# MT-DS_v1.net
KiCad netlist of a schematic drawn in EAGLE
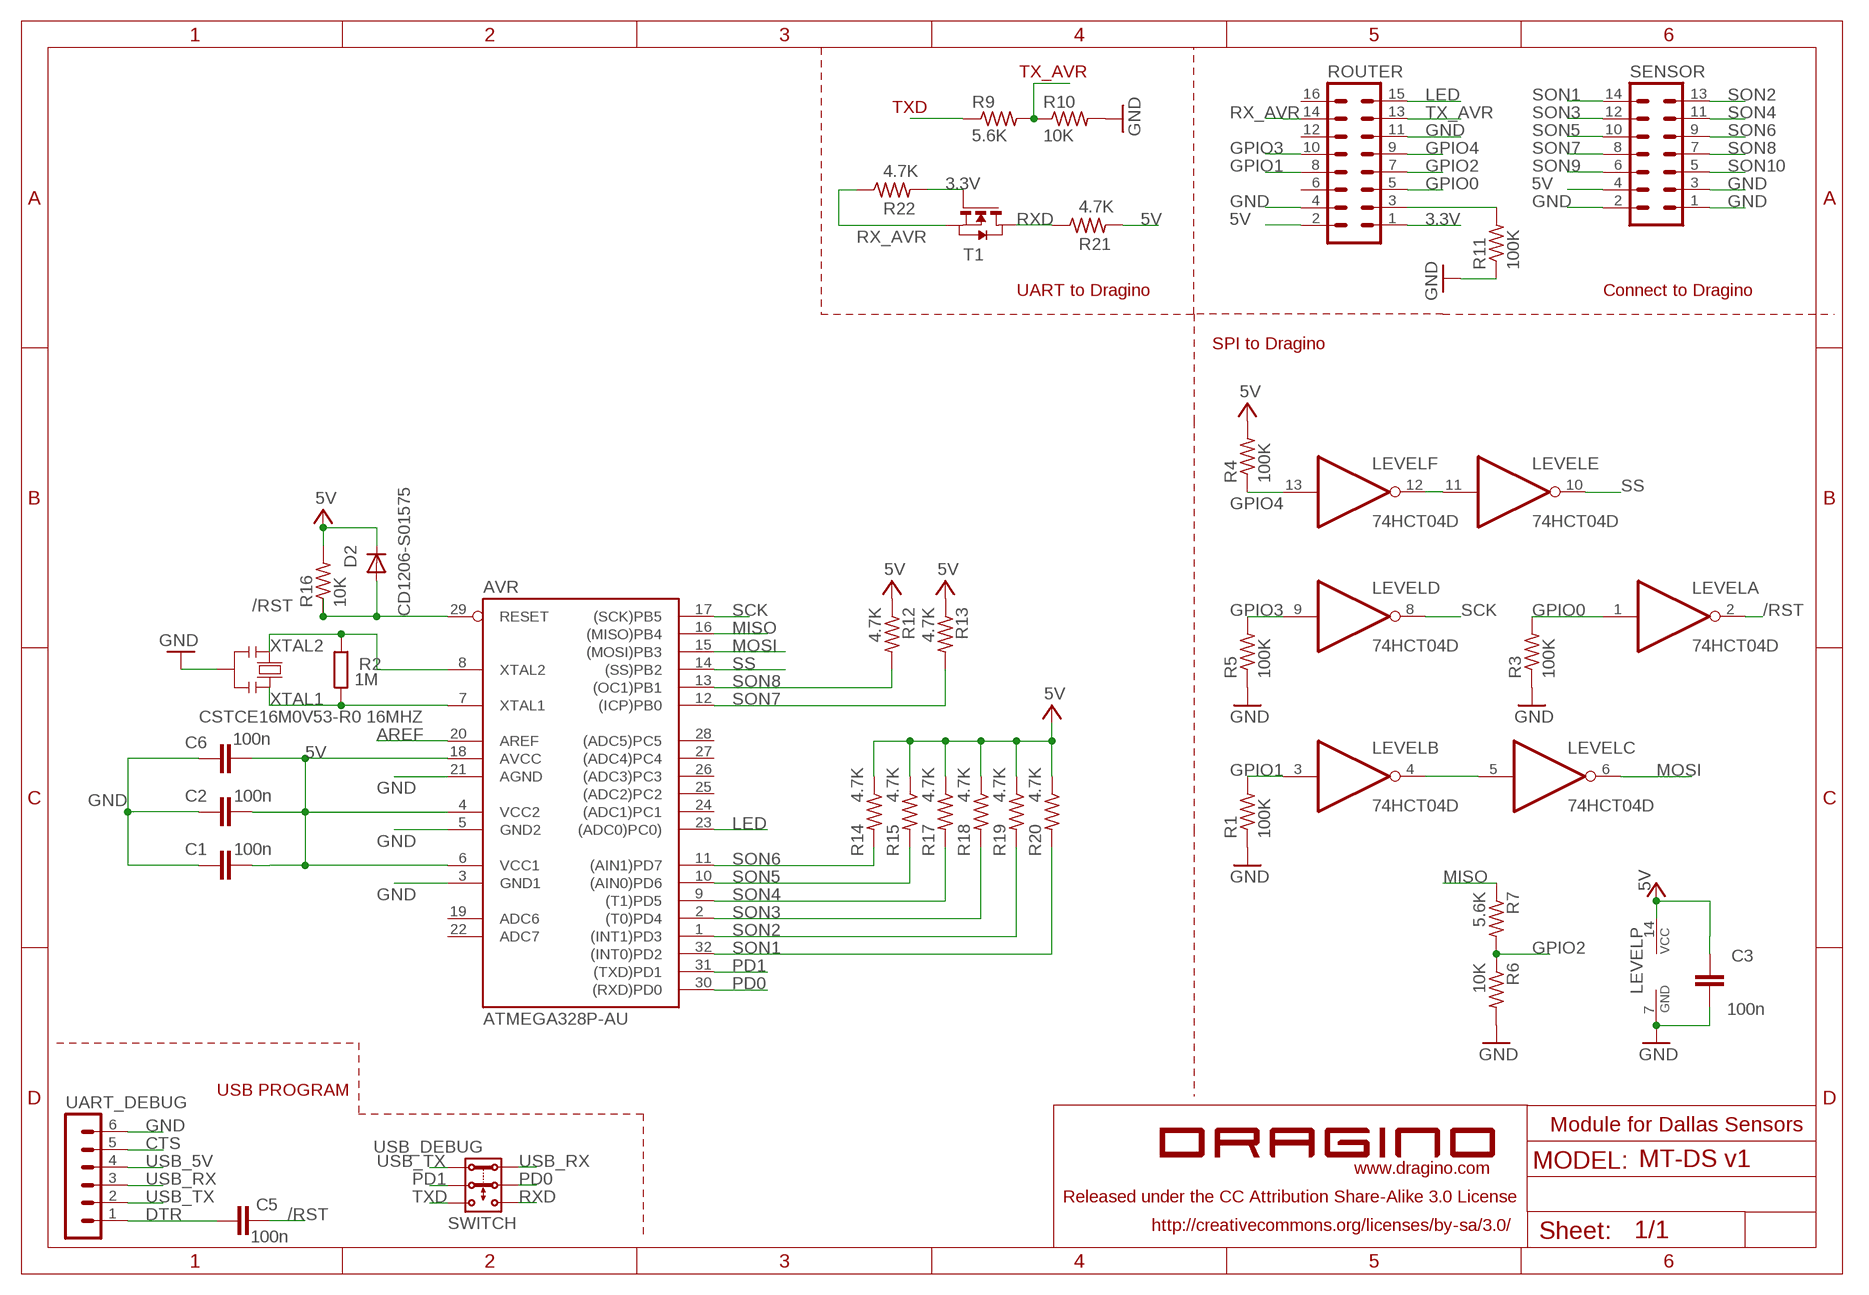
[diagram p0: schematic, sheet 1]

(export (version "E")
  (design (tool "Eeschema 10.0.6"))
  (components
    (comp (ref "AVR")
      (value "ATMEGA328P-AU")
      (footprint "eagle-import:SMARTPRJ_TQFP32-08")
      (libsource (lib "eagle-import") (part "SMARTPRJ_ATMEGA328P-AU"))
    )
    (comp (ref "C1")
      (value "100n")
      (footprint "eagle-import:C0402")
      (libsource (lib "eagle-import") (part "C-EUC0402"))
    )
    (comp (ref "C2")
      (value "100n")
      (footprint "eagle-import:C0402")
      (libsource (lib "eagle-import") (part "C-EUC0402"))
    )
    (comp (ref "C3")
      (value "100n")
      (footprint "eagle-import:C0402")
      (libsource (lib "eagle-import") (part "C-EUC0402"))
    )
    (comp (ref "C5")
      (value "100n")
      (footprint "eagle-import:C0402")
      (libsource (lib "eagle-import") (part "C-EUC0402"))
    )
    (comp (ref "C6")
      (value "100n")
      (footprint "eagle-import:C0402")
      (libsource (lib "eagle-import") (part "C-EUC0402"))
    )
    (comp (ref "D2")
      (value "CD1206-S01575")
      (footprint "eagle-import:MINIMELF")
      (libsource (lib "eagle-import") (part "DIODE-MINIMELF"))
    )
    (comp (ref "LEVEL")
      (value "74HCT04D")
      (footprint "eagle-import:SO14")
      (libsource (lib "eagle-import") (part "7404DHCT"))
    )
    (comp (ref "R1")
      (value "100K")
      (footprint "eagle-import:R0402")
      (libsource (lib "eagle-import") (part "R-US_R0402"))
    )
    (comp (ref "R2")
      (value "1M")
      (footprint "eagle-import:R0402")
      (libsource (lib "eagle-import") (part "R-EU_R0402"))
    )
    (comp (ref "R3")
      (value "100K")
      (footprint "eagle-import:R0402")
      (libsource (lib "eagle-import") (part "R-US_R0402"))
    )
    (comp (ref "R4")
      (value "100K")
      (footprint "eagle-import:R0402")
      (libsource (lib "eagle-import") (part "R-US_R0402"))
    )
    (comp (ref "R5")
      (value "100K")
      (footprint "eagle-import:R0402")
      (libsource (lib "eagle-import") (part "R-US_R0402"))
    )
    (comp (ref "R6")
      (value "10K")
      (footprint "eagle-import:R0402")
      (libsource (lib "eagle-import") (part "R-US_R0402"))
    )
    (comp (ref "R7")
      (value "5.6K")
      (footprint "eagle-import:R0402")
      (libsource (lib "eagle-import") (part "R-US_R0402"))
    )
    (comp (ref "R9")
      (value "5.6K")
      (footprint "eagle-import:R0402")
      (libsource (lib "eagle-import") (part "R-US_R0402"))
    )
    (comp (ref "R10")
      (value "10K")
      (footprint "eagle-import:R0402")
      (libsource (lib "eagle-import") (part "R-US_R0402"))
    )
    (comp (ref "R11")
      (value "100K")
      (footprint "eagle-import:R0402")
      (libsource (lib "eagle-import") (part "R-US_R0402"))
    )
    (comp (ref "R12")
      (value "4.7K")
      (footprint "eagle-import:R0805")
      (libsource (lib "eagle-import") (part "R-US_R0805"))
    )
    (comp (ref "R13")
      (value "4.7K")
      (footprint "eagle-import:R0805")
      (libsource (lib "eagle-import") (part "R-US_R0805"))
    )
    (comp (ref "R14")
      (value "4.7K")
      (footprint "eagle-import:R0805")
      (libsource (lib "eagle-import") (part "R-US_R0805"))
    )
    (comp (ref "R15")
      (value "4.7K")
      (footprint "eagle-import:R0805")
      (libsource (lib "eagle-import") (part "R-US_R0805"))
    )
    (comp (ref "R16")
      (value "10K")
      (footprint "eagle-import:R0402")
      (libsource (lib "eagle-import") (part "R-US_R0402"))
    )
    (comp (ref "R17")
      (value "4.7K")
      (footprint "eagle-import:R0805")
      (libsource (lib "eagle-import") (part "R-US_R0805"))
    )
    (comp (ref "R18")
      (value "4.7K")
      (footprint "eagle-import:R0805")
      (libsource (lib "eagle-import") (part "R-US_R0805"))
    )
    (comp (ref "R19")
      (value "4.7K")
      (footprint "eagle-import:R0805")
      (libsource (lib "eagle-import") (part "R-US_R0805"))
    )
    (comp (ref "R20")
      (value "4.7K")
      (footprint "eagle-import:R0805")
      (libsource (lib "eagle-import") (part "R-US_R0805"))
    )
    (comp (ref "R21")
      (value "4.7K")
      (footprint "eagle-import:R0805")
      (libsource (lib "eagle-import") (part "R-US_R0805"))
    )
    (comp (ref "R22")
      (value "4.7K")
      (footprint "eagle-import:R0805")
      (libsource (lib "eagle-import") (part "R-US_R0805"))
    )
    (comp (ref "ROUTER")
      (value "MA08-2")
      (footprint "eagle-import:MA08-2")
      (libsource (lib "eagle-import") (part "MA08-2"))
    )
    (comp (ref "SENSOR")
      (value "MA07-2")
      (footprint "eagle-import:MA07-2")
      (libsource (lib "eagle-import") (part "MA07-2"))
    )
    (comp (ref "T1")
      (value "NMOSFET-SOT23")
      (footprint "eagle-import:SOT-23")
      (libsource (lib "eagle-import") (part "NMOSFET-SOT23"))
    )
    (comp (ref "U$1")
      (value "LOGO-SILK")
      (footprint "eagle-import:LOGO-SILK-15MM")
      (libsource (lib "eagle-import") (part "LOGO-SILK"))
    )
    (comp (ref "UART_DEBUG")
      (value "MA06-1")
      (footprint "eagle-import:MA06-1")
      (libsource (lib "eagle-import") (part "MA06-1"))
    )
    (comp (ref "USB_DEBUG")
      (value "SWITCH")
      (footprint "eagle-import:2P2T")
      (libsource (lib "eagle-import") (part "SWITCH-2P2T"))
    )
    (comp (ref "Y2")
      (value "CSTCE16M0V53-R0 16MHZ")
      (footprint "eagle-import:RESONATOR")
      (libsource (lib "eagle-import") (part "RESONATORMU"))
    )
  )
  (nets
    (net (code "1") (name "/3.3V") (class "Default")
      (node (ref "R22") (pin "2") (pinfunction "2_2") (pintype "passive"))
      (node (ref "ROUTER") (pin "1") (pinfunction "1_1") (pintype "passive"))
      (node (ref "T1") (pin "3") (pinfunction "G_3") (pintype "passive"))
    )
    (net (code "2") (name "/AREF") (class "Default")
      (node (ref "AVR") (pin "20") (pinfunction "AREF_20") (pintype "passive"))
    )
    (net (code "3") (name "/CTS") (class "Default")
      (node (ref "UART_DEBUG") (pin "5") (pinfunction "5_5") (pintype "passive"))
    )
    (net (code "4") (name "/DTR") (class "Default")
      (node (ref "C5") (pin "1") (pinfunction "1_1") (pintype "passive"))
      (node (ref "UART_DEBUG") (pin "1") (pinfunction "1_1") (pintype "passive"))
    )
    (net (code "5") (name "/GPIO0") (class "Default")
      (node (ref "LEVEL") (pin "1") (pinfunction "I_1") (pintype "input"))
      (node (ref "R3") (pin "2") (pinfunction "2_2") (pintype "passive"))
      (node (ref "ROUTER") (pin "5") (pinfunction "5_5") (pintype "passive"))
    )
    (net (code "6") (name "/GPIO1") (class "Default")
      (node (ref "LEVEL") (pin "3") (pinfunction "I_3") (pintype "input"))
      (node (ref "R1") (pin "2") (pinfunction "2_2") (pintype "passive"))
      (node (ref "ROUTER") (pin "8") (pinfunction "8_8") (pintype "passive"))
    )
    (net (code "7") (name "/GPIO2") (class "Default")
      (node (ref "R6") (pin "1") (pinfunction "1_1") (pintype "passive"))
      (node (ref "R7") (pin "2") (pinfunction "2_2") (pintype "passive"))
      (node (ref "ROUTER") (pin "7") (pinfunction "7_7") (pintype "passive"))
    )
    (net (code "8") (name "/GPIO3") (class "Default")
      (node (ref "LEVEL") (pin "9") (pinfunction "I_9") (pintype "input"))
      (node (ref "R5") (pin "2") (pinfunction "2_2") (pintype "passive"))
      (node (ref "ROUTER") (pin "10") (pinfunction "10_10") (pintype "passive"))
    )
    (net (code "9") (name "/GPIO4") (class "Default")
      (node (ref "LEVEL") (pin "13") (pinfunction "I_13") (pintype "input"))
      (node (ref "R4") (pin "1") (pinfunction "1_1") (pintype "passive"))
      (node (ref "ROUTER") (pin "9") (pinfunction "9_9") (pintype "passive"))
    )
    (net (code "10") (name "/LED") (class "Default")
      (node (ref "AVR") (pin "23") (pinfunction "(ADC0)PC0)_23") (pintype "bidirectional"))
      (node (ref "ROUTER") (pin "15") (pinfunction "15_15") (pintype "passive"))
    )
    (net (code "11") (name "/MISO") (class "Default")
      (node (ref "AVR") (pin "16") (pinfunction "(MISO)PB4_16") (pintype "bidirectional"))
      (node (ref "R7") (pin "1") (pinfunction "1_1") (pintype "passive"))
    )
    (net (code "12") (name "/MOSI") (class "Default")
      (node (ref "AVR") (pin "15") (pinfunction "(MOSI)PB3_15") (pintype "bidirectional"))
      (node (ref "LEVEL") (pin "6") (pinfunction "O_6") (pintype "output"))
    )
    (net (code "13") (name "/PD0") (class "Default")
      (node (ref "AVR") (pin "30") (pinfunction "(RXD)PD0_30") (pintype "bidirectional"))
      (node (ref "USB_DEBUG") (pin "2.1") (pinfunction "2.1_2.1") (pintype "passive"))
    )
    (net (code "14") (name "/PD1") (class "Default")
      (node (ref "AVR") (pin "31") (pinfunction "(TXD)PD1_31") (pintype "bidirectional"))
      (node (ref "USB_DEBUG") (pin "2.2") (pinfunction "2.2_2.2") (pintype "passive"))
    )
    (net (code "15") (name "/RXD") (class "Default")
      (node (ref "R21") (pin "1") (pinfunction "1_1") (pintype "passive"))
      (node (ref "T1") (pin "1") (pinfunction "D_1") (pintype "passive"))
      (node (ref "USB_DEBUG") (pin "3.1") (pinfunction "3.1_3.1") (pintype "passive"))
    )
    (net (code "16") (name "/RX_AVR") (class "Default")
      (node (ref "R22") (pin "1") (pinfunction "1_1") (pintype "passive"))
      (node (ref "ROUTER") (pin "14") (pinfunction "14_14") (pintype "passive"))
      (node (ref "T1") (pin "2") (pinfunction "S_2") (pintype "passive"))
    )
    (net (code "17") (name "/SCK") (class "Default")
      (node (ref "AVR") (pin "17") (pinfunction "(SCK)PB5_17") (pintype "bidirectional"))
      (node (ref "LEVEL") (pin "8") (pinfunction "O_8") (pintype "output"))
    )
    (net (code "18") (name "/SON1") (class "Default")
      (node (ref "AVR") (pin "32") (pinfunction "(INT0)PD2_32") (pintype "bidirectional"))
      (node (ref "R20") (pin "2") (pinfunction "2_2") (pintype "passive"))
      (node (ref "SENSOR") (pin "14") (pinfunction "14_14") (pintype "passive"))
    )
    (net (code "19") (name "/SON2") (class "Default")
      (node (ref "AVR") (pin "1") (pinfunction "(INT1)PD3_1") (pintype "bidirectional"))
      (node (ref "R19") (pin "2") (pinfunction "2_2") (pintype "passive"))
      (node (ref "SENSOR") (pin "13") (pinfunction "13_13") (pintype "passive"))
    )
    (net (code "20") (name "/SON3") (class "Default")
      (node (ref "AVR") (pin "2") (pinfunction "(T0)PD4_2") (pintype "bidirectional"))
      (node (ref "R18") (pin "2") (pinfunction "2_2") (pintype "passive"))
      (node (ref "SENSOR") (pin "12") (pinfunction "12_12") (pintype "passive"))
    )
    (net (code "21") (name "/SON4") (class "Default")
      (node (ref "AVR") (pin "9") (pinfunction "(T1)PD5_9") (pintype "bidirectional"))
      (node (ref "R17") (pin "2") (pinfunction "2_2") (pintype "passive"))
      (node (ref "SENSOR") (pin "11") (pinfunction "11_11") (pintype "passive"))
    )
    (net (code "22") (name "/SON5") (class "Default")
      (node (ref "AVR") (pin "10") (pinfunction "(AIN0)PD6_10") (pintype "bidirectional"))
      (node (ref "R15") (pin "2") (pinfunction "2_2") (pintype "passive"))
      (node (ref "SENSOR") (pin "10") (pinfunction "10_10") (pintype "passive"))
    )
    (net (code "23") (name "/SON6") (class "Default")
      (node (ref "AVR") (pin "11") (pinfunction "(AIN1)PD7_11") (pintype "bidirectional"))
      (node (ref "R14") (pin "2") (pinfunction "2_2") (pintype "passive"))
      (node (ref "SENSOR") (pin "9") (pinfunction "9_9") (pintype "passive"))
    )
    (net (code "24") (name "/SON7") (class "Default")
      (node (ref "AVR") (pin "12") (pinfunction "(ICP)PB0_12") (pintype "bidirectional"))
      (node (ref "R13") (pin "2") (pinfunction "2_2") (pintype "passive"))
      (node (ref "SENSOR") (pin "8") (pinfunction "8_8") (pintype "passive"))
    )
    (net (code "25") (name "/SON8") (class "Default")
      (node (ref "AVR") (pin "13") (pinfunction "(OC1)PB1_13") (pintype "bidirectional"))
      (node (ref "R12") (pin "2") (pinfunction "2_2") (pintype "passive"))
      (node (ref "SENSOR") (pin "7") (pinfunction "7_7") (pintype "passive"))
    )
    (net (code "26") (name "/SON9") (class "Default")
      (node (ref "SENSOR") (pin "6") (pinfunction "6_6") (pintype "passive"))
    )
    (net (code "27") (name "/SON10") (class "Default")
      (node (ref "SENSOR") (pin "5") (pinfunction "5_5") (pintype "passive"))
    )
    (net (code "28") (name "/SS") (class "Default")
      (node (ref "AVR") (pin "14") (pinfunction "(SS)PB2_14") (pintype "bidirectional"))
      (node (ref "LEVEL") (pin "10") (pinfunction "O_10") (pintype "output"))
    )
    (net (code "29") (name "/TXD") (class "Default")
      (node (ref "R9") (pin "1") (pinfunction "1_1") (pintype "passive"))
      (node (ref "USB_DEBUG") (pin "3.2") (pinfunction "3.2_3.2") (pintype "passive"))
    )
    (net (code "30") (name "/TX_AVR") (class "Default")
      (node (ref "R10") (pin "1") (pinfunction "1_1") (pintype "passive"))
      (node (ref "R9") (pin "2") (pinfunction "2_2") (pintype "passive"))
      (node (ref "ROUTER") (pin "13") (pinfunction "13_13") (pintype "passive"))
    )
    (net (code "31") (name "/USB_5V") (class "Default")
      (node (ref "UART_DEBUG") (pin "4") (pinfunction "4_4") (pintype "passive"))
    )
    (net (code "32") (name "/USB_RX") (class "Default")
      (node (ref "UART_DEBUG") (pin "3") (pinfunction "3_3") (pintype "passive"))
      (node (ref "USB_DEBUG") (pin "1.1") (pinfunction "1.1_1.1") (pintype "passive"))
    )
    (net (code "33") (name "/USB_TX") (class "Default")
      (node (ref "UART_DEBUG") (pin "2") (pinfunction "2_2") (pintype "passive"))
      (node (ref "USB_DEBUG") (pin "1.2") (pinfunction "1.2_1.2") (pintype "passive"))
    )
    (net (code "34") (name "/XTAL1") (class "Default")
      (node (ref "AVR") (pin "7") (pinfunction "XTAL1_7") (pintype "bidirectional"))
      (node (ref "R2") (pin "1") (pinfunction "1_1") (pintype "passive"))
      (node (ref "Y2") (pin "3") (pinfunction "3_3") (pintype "passive"))
    )
    (net (code "35") (name "/XTAL2") (class "Default")
      (node (ref "AVR") (pin "8") (pinfunction "XTAL2_8") (pintype "bidirectional"))
      (node (ref "R2") (pin "2") (pinfunction "2_2") (pintype "passive"))
      (node (ref "Y2") (pin "1") (pinfunction "1_1") (pintype "passive"))
    )
    (net (code "36") (name "/{slash}RST") (class "Default")
      (node (ref "AVR") (pin "29") (pinfunction "RESET_29") (pintype "input"))
      (node (ref "C5") (pin "2") (pinfunction "2_2") (pintype "passive"))
      (node (ref "D2") (pin "A") (pinfunction "A_A") (pintype "passive"))
      (node (ref "LEVEL") (pin "2") (pinfunction "O_2") (pintype "output"))
      (node (ref "R16") (pin "1") (pinfunction "1_1") (pintype "passive"))
    )
    (net (code "37") (name "5V") (class "Default")
      (node (ref "AVR") (pin "18") (pinfunction "AVCC_18") (pintype "power_in"))
      (node (ref "AVR") (pin "4") (pinfunction "VCC2_4") (pintype "power_in"))
      (node (ref "AVR") (pin "6") (pinfunction "VCC1_6") (pintype "power_in"))
      (node (ref "C1") (pin "1") (pinfunction "1_1") (pintype "passive"))
      (node (ref "C2") (pin "1") (pinfunction "1_1") (pintype "passive"))
      (node (ref "C3") (pin "2") (pinfunction "2_2") (pintype "passive"))
      (node (ref "C6") (pin "1") (pinfunction "1_1") (pintype "passive"))
      (node (ref "D2") (pin "C") (pinfunction "C_C") (pintype "passive"))
      (node (ref "LEVEL") (pin "14") (pinfunction "VCC_14") (pintype "power_in"))
      (node (ref "R12") (pin "1") (pinfunction "1_1") (pintype "passive"))
      (node (ref "R13") (pin "1") (pinfunction "1_1") (pintype "passive"))
      (node (ref "R14") (pin "1") (pinfunction "1_1") (pintype "passive"))
      (node (ref "R15") (pin "1") (pinfunction "1_1") (pintype "passive"))
      (node (ref "R16") (pin "2") (pinfunction "2_2") (pintype "passive"))
      (node (ref "R17") (pin "1") (pinfunction "1_1") (pintype "passive"))
      (node (ref "R18") (pin "1") (pinfunction "1_1") (pintype "passive"))
      (node (ref "R19") (pin "1") (pinfunction "1_1") (pintype "passive"))
      (node (ref "R20") (pin "1") (pinfunction "1_1") (pintype "passive"))
      (node (ref "R21") (pin "2") (pinfunction "2_2") (pintype "passive"))
      (node (ref "R4") (pin "2") (pinfunction "2_2") (pintype "passive"))
      (node (ref "ROUTER") (pin "2") (pinfunction "2_2") (pintype "passive"))
      (node (ref "SENSOR") (pin "4") (pinfunction "4_4") (pintype "passive"))
    )
    (net (code "38") (name "GND") (class "Default")
      (node (ref "AVR") (pin "21") (pinfunction "AGND_21") (pintype "power_in"))
      (node (ref "AVR") (pin "3") (pinfunction "GND1_3") (pintype "power_in"))
      (node (ref "AVR") (pin "5") (pinfunction "GND2_5") (pintype "power_in"))
      (node (ref "C1") (pin "2") (pinfunction "2_2") (pintype "passive"))
      (node (ref "C2") (pin "2") (pinfunction "2_2") (pintype "passive"))
      (node (ref "C3") (pin "1") (pinfunction "1_1") (pintype "passive"))
      (node (ref "C6") (pin "2") (pinfunction "2_2") (pintype "passive"))
      (node (ref "LEVEL") (pin "7") (pinfunction "GND_7") (pintype "power_in"))
      (node (ref "R1") (pin "1") (pinfunction "1_1") (pintype "passive"))
      (node (ref "R10") (pin "2") (pinfunction "2_2") (pintype "passive"))
      (node (ref "R11") (pin "1") (pinfunction "1_1") (pintype "passive"))
      (node (ref "R3") (pin "1") (pinfunction "1_1") (pintype "passive"))
      (node (ref "R5") (pin "1") (pinfunction "1_1") (pintype "passive"))
      (node (ref "R6") (pin "2") (pinfunction "2_2") (pintype "passive"))
      (node (ref "ROUTER") (pin "11") (pinfunction "11_11") (pintype "passive"))
      (node (ref "ROUTER") (pin "4") (pinfunction "4_4") (pintype "passive"))
      (node (ref "SENSOR") (pin "1") (pinfunction "1_1") (pintype "passive"))
      (node (ref "SENSOR") (pin "2") (pinfunction "2_2") (pintype "passive"))
      (node (ref "SENSOR") (pin "3") (pinfunction "3_3") (pintype "passive"))
      (node (ref "UART_DEBUG") (pin "6") (pinfunction "6_6") (pintype "passive"))
      (node (ref "Y2") (pin "2") (pinfunction "2_2") (pintype "passive"))
    )
    (net (code "39") (name "Net-(LEVELB-O)") (class "Default")
      (node (ref "LEVEL") (pin "4") (pinfunction "O_4") (pintype "output"))
      (node (ref "LEVEL") (pin "5") (pinfunction "I_5") (pintype "input"))
    )
    (net (code "40") (name "Net-(LEVELE-I)") (class "Default")
      (node (ref "LEVEL") (pin "11") (pinfunction "I_11") (pintype "input"))
      (node (ref "LEVEL") (pin "12") (pinfunction "O_12") (pintype "output"))
    )
    (net (code "41") (name "Net-(R11-Pad2)") (class "Default")
      (node (ref "R11") (pin "2") (pinfunction "2_2") (pintype "passive"))
      (node (ref "ROUTER") (pin "3") (pinfunction "3_3") (pintype "passive"))
    )
    (net (code "42") (name "unconnected-(AVR-(ADC1)PC1-Pad24)") (class "Default")
      (node (ref "AVR") (pin "24") (pinfunction "(ADC1)PC1_24") (pintype "bidirectional"))
    )
    (net (code "43") (name "unconnected-(AVR-(ADC2)PC2-Pad25)") (class "Default")
      (node (ref "AVR") (pin "25") (pinfunction "(ADC2)PC2_25") (pintype "bidirectional"))
    )
    (net (code "44") (name "unconnected-(AVR-(ADC3)PC3-Pad26)") (class "Default")
      (node (ref "AVR") (pin "26") (pinfunction "(ADC3)PC3_26") (pintype "bidirectional"))
    )
    (net (code "45") (name "unconnected-(AVR-(ADC4)PC4-Pad27)") (class "Default")
      (node (ref "AVR") (pin "27") (pinfunction "(ADC4)PC4_27") (pintype "bidirectional"))
    )
    (net (code "46") (name "unconnected-(AVR-(ADC5)PC5-Pad28)") (class "Default")
      (node (ref "AVR") (pin "28") (pinfunction "(ADC5)PC5_28") (pintype "bidirectional"))
    )
    (net (code "47") (name "unconnected-(AVR-ADC6-Pad19)") (class "Default")
      (node (ref "AVR") (pin "19") (pinfunction "ADC6_19") (pintype "bidirectional"))
    )
    (net (code "48") (name "unconnected-(AVR-ADC7-Pad22)") (class "Default")
      (node (ref "AVR") (pin "22") (pinfunction "ADC7_22") (pintype "bidirectional"))
    )
    (net (code "49") (name "unconnected-(ROUTER-Pad6)") (class "Default")
      (node (ref "ROUTER") (pin "6") (pinfunction "6_6") (pintype "passive"))
    )
    (net (code "50") (name "unconnected-(ROUTER-Pad12)") (class "Default")
      (node (ref "ROUTER") (pin "12") (pinfunction "12_12") (pintype "passive"))
    )
    (net (code "51") (name "unconnected-(ROUTER-Pad16)") (class "Default")
      (node (ref "ROUTER") (pin "16") (pinfunction "16_16") (pintype "passive"))
    )
  )
)
